# LPT3_5.net
KiCad netlist of a schematic drawn in EAGLE
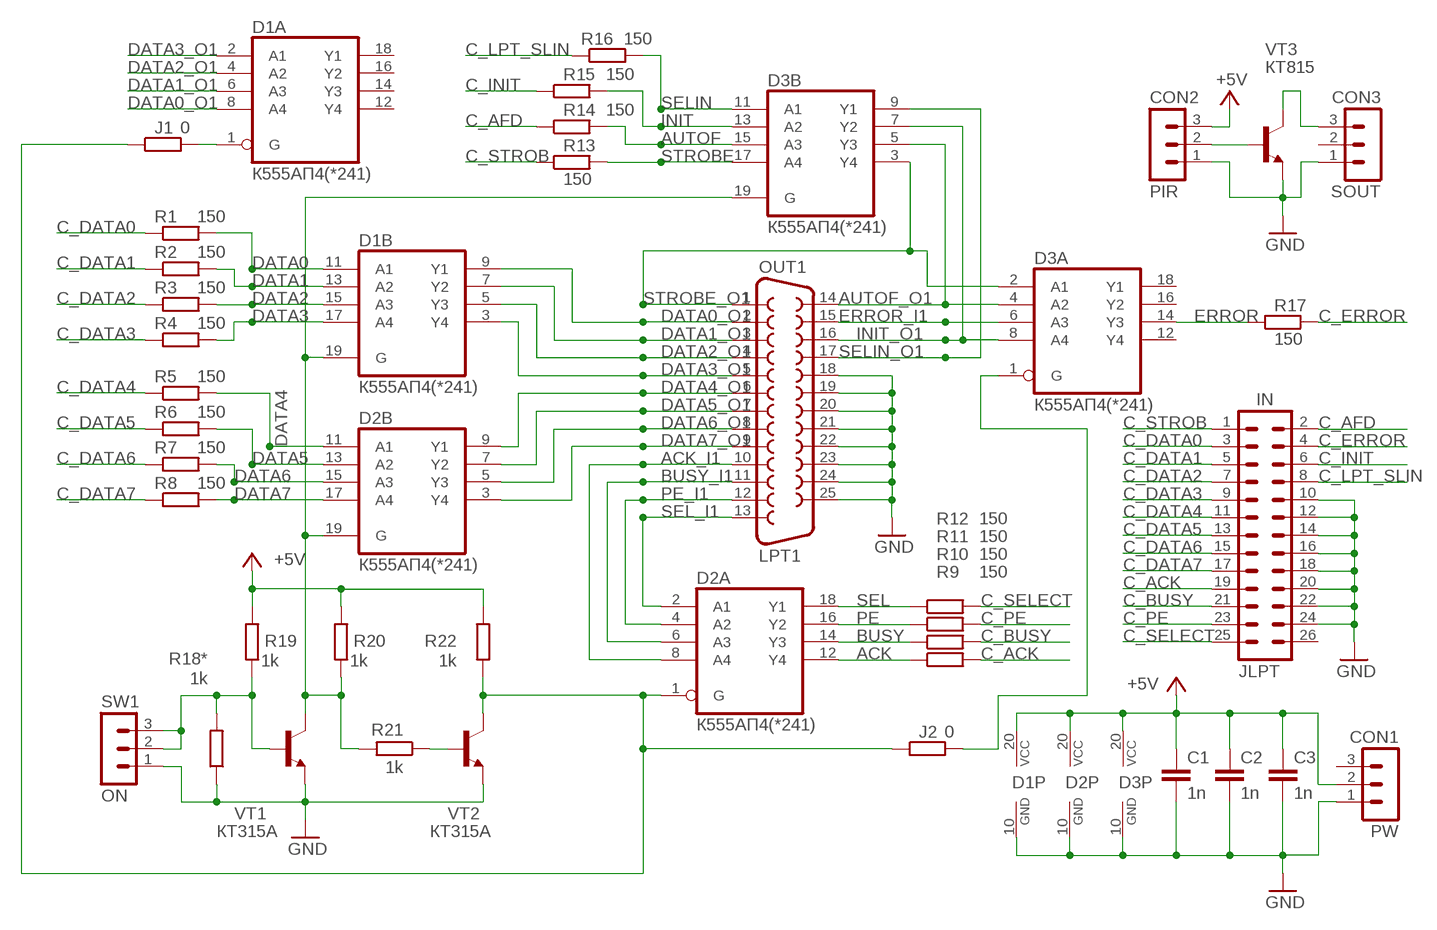
[diagram p0: schematic, sheet 1]

(export (version "E")
  (design (tool "Eeschema 10.0.6"))
  (components
    (comp (ref "C1")
      (value "1n")
      (footprint "eagle-import:C050-024X044")
      (libsource (lib "eagle-import") (part "C-EU050-024X044"))
    )
    (comp (ref "C2")
      (value "1n")
      (footprint "eagle-import:C075-032X103")
      (libsource (lib "eagle-import") (part "C-EU075-032X103"))
    )
    (comp (ref "C3")
      (value "1n")
      (footprint "eagle-import:C050-024X044")
      (libsource (lib "eagle-import") (part "C-EU050-024X044"))
    )
    (comp (ref "CON1")
      (value "PW")
      (footprint "eagle-import:MA03-1")
      (fields (field (name "OC_FARNELL") "unknown") (field (name "OC_NEWARK") "unknown"))
      (libsource (lib "eagle-import") (part "MA03-1"))
    )
    (comp (ref "CON2")
      (value "PIR")
      (footprint "eagle-import:MA03-1")
      (fields (field (name "OC_FARNELL") "unknown") (field (name "OC_NEWARK") "unknown"))
      (libsource (lib "eagle-import") (part "MA03-1"))
    )
    (comp (ref "CON3")
      (value "SOUT")
      (footprint "eagle-import:MA03-1")
      (fields (field (name "OC_FARNELL") "unknown") (field (name "OC_NEWARK") "unknown"))
      (libsource (lib "eagle-import") (part "MA03-1"))
    )
    (comp (ref "D1")
      (value "К555АП4(*241)")
      (footprint "eagle-import:DIL20")
      (libsource (lib "eagle-import") (part "74241NAC"))
    )
    (comp (ref "D2")
      (value "К555АП4(*241)")
      (footprint "eagle-import:DIL20")
      (libsource (lib "eagle-import") (part "74241NAC"))
    )
    (comp (ref "D3")
      (value "К555АП4(*241)")
      (footprint "eagle-import:DIL20")
      (libsource (lib "eagle-import") (part "74241NAC"))
    )
    (comp (ref "IN")
      (value "JLPT")
      (footprint "eagle-import:MA13-2")
      (libsource (lib "eagle-import") (part "MA13-2"))
    )
    (comp (ref "J1")
      (value "0")
      (footprint "eagle-import:R1206")
      (libsource (lib "eagle-import") (part "R-EU_R1206"))
    )
    (comp (ref "J2")
      (value "0")
      (footprint "eagle-import:R1206")
      (libsource (lib "eagle-import") (part "R-EU_R1206"))
    )
    (comp (ref "OUT1")
      (value "LPT1")
      (footprint "eagle-import:F25HP")
      (libsource (lib "eagle-import") (part "F25HP"))
    )
    (comp (ref "R1")
      (value "150")
      (footprint "eagle-import:0204_7")
      (libsource (lib "eagle-import") (part "R-EU_0204/7"))
    )
    (comp (ref "R2")
      (value "150")
      (footprint "eagle-import:0204_7")
      (libsource (lib "eagle-import") (part "R-EU_0204/7"))
    )
    (comp (ref "R3")
      (value "150")
      (footprint "eagle-import:0204_7")
      (libsource (lib "eagle-import") (part "R-EU_0204/7"))
    )
    (comp (ref "R4")
      (value "150")
      (footprint "eagle-import:0204_7")
      (libsource (lib "eagle-import") (part "R-EU_0204/7"))
    )
    (comp (ref "R5")
      (value "150")
      (footprint "eagle-import:0204_7")
      (libsource (lib "eagle-import") (part "R-EU_0204/7"))
    )
    (comp (ref "R6")
      (value "150")
      (footprint "eagle-import:0204_7")
      (libsource (lib "eagle-import") (part "R-EU_0204/7"))
    )
    (comp (ref "R7")
      (value "150")
      (footprint "eagle-import:0204_7")
      (libsource (lib "eagle-import") (part "R-EU_0204/7"))
    )
    (comp (ref "R8")
      (value "150")
      (footprint "eagle-import:0204_7")
      (libsource (lib "eagle-import") (part "R-EU_0204/7"))
    )
    (comp (ref "R9")
      (value "150")
      (footprint "eagle-import:0204_7")
      (libsource (lib "eagle-import") (part "R-EU_0204/7"))
    )
    (comp (ref "R10")
      (value "150")
      (footprint "eagle-import:0204_7")
      (libsource (lib "eagle-import") (part "R-EU_0204/7"))
    )
    (comp (ref "R11")
      (value "150")
      (footprint "eagle-import:0204_7")
      (libsource (lib "eagle-import") (part "R-EU_0204/7"))
    )
    (comp (ref "R12")
      (value "150")
      (footprint "eagle-import:0204_7")
      (libsource (lib "eagle-import") (part "R-EU_0204/7"))
    )
    (comp (ref "R13")
      (value "150")
      (footprint "eagle-import:M0805")
      (libsource (lib "eagle-import") (part "R-EU_M0805"))
    )
    (comp (ref "R14")
      (value "150")
      (footprint "eagle-import:M0805")
      (libsource (lib "eagle-import") (part "R-EU_M0805"))
    )
    (comp (ref "R15")
      (value "150")
      (footprint "eagle-import:M0805")
      (libsource (lib "eagle-import") (part "R-EU_M0805"))
    )
    (comp (ref "R16")
      (value "150")
      (footprint "eagle-import:M0805")
      (libsource (lib "eagle-import") (part "R-EU_M0805"))
    )
    (comp (ref "R17")
      (value "150")
      (footprint "eagle-import:M0805")
      (libsource (lib "eagle-import") (part "R-EU_M0805"))
    )
    (comp (ref "R18*")
      (value "1k")
      (footprint "eagle-import:M0805")
      (libsource (lib "eagle-import") (part "R-EU_M0805"))
    )
    (comp (ref "R19")
      (value "1k")
      (footprint "eagle-import:M1206")
      (libsource (lib "eagle-import") (part "R-EU_M1206"))
    )
    (comp (ref "R20")
      (value "1k")
      (footprint "eagle-import:M0805")
      (libsource (lib "eagle-import") (part "R-EU_M0805"))
    )
    (comp (ref "R21")
      (value "1k")
      (footprint "eagle-import:M0805")
      (libsource (lib "eagle-import") (part "R-EU_M0805"))
    )
    (comp (ref "R22")
      (value "1k")
      (footprint "eagle-import:M0805")
      (libsource (lib "eagle-import") (part "R-EU_M0805"))
    )
    (comp (ref "SW1")
      (value "ON")
      (footprint "eagle-import:MA03-1")
      (libsource (lib "eagle-import") (part "MA03-1"))
    )
    (comp (ref "VT1")
      (value "КТ315А")
      (footprint "eagle-import:TO92-ECB")
      (libsource (lib "eagle-import") (part "2SC1740"))
    )
    (comp (ref "VT2")
      (value "КТ315А")
      (footprint "eagle-import:TO92-ECB")
      (libsource (lib "eagle-import") (part "2SC1740"))
    )
    (comp (ref "VT3")
      (value "КТ815")
      (footprint "eagle-import:TO220BV")
      (libsource (lib "eagle-import") (part "2SC1306"))
    )
  )
  (nets
    (net (code "1") (name "+5V") (class "Default")
      (node (ref "C1") (pin "1") (pinfunction "1_1") (pintype "passive"))
      (node (ref "C2") (pin "1") (pinfunction "1_1") (pintype "passive"))
      (node (ref "C3") (pin "1") (pinfunction "1_1") (pintype "passive"))
      (node (ref "CON1") (pin "2") (pinfunction "2_2") (pintype "passive"))
      (node (ref "CON2") (pin "3") (pinfunction "3_3") (pintype "passive"))
      (node (ref "D1") (pin "20") (pinfunction "VCC_20") (pintype "power_in"))
      (node (ref "D2") (pin "20") (pinfunction "VCC_20") (pintype "power_in"))
      (node (ref "D3") (pin "20") (pinfunction "VCC_20") (pintype "power_in"))
      (node (ref "R19") (pin "2") (pinfunction "2_2") (pintype "passive"))
      (node (ref "R20") (pin "2") (pinfunction "2_2") (pintype "passive"))
      (node (ref "R22") (pin "2") (pinfunction "2_2") (pintype "passive"))
    )
    (net (code "2") (name "/ACK") (class "Default")
      (node (ref "D2") (pin "12") (pinfunction "Y4_12") (pintype "tri_state"))
      (node (ref "R9") (pin "1") (pinfunction "1_1") (pintype "passive"))
    )
    (net (code "3") (name "/ACK_I1") (class "Default")
      (node (ref "D2") (pin "8") (pinfunction "A4_8") (pintype "input"))
      (node (ref "OUT1") (pin "10") (pinfunction "10_10") (pintype "passive"))
    )
    (net (code "4") (name "/AUTOF") (class "Default")
      (node (ref "D3") (pin "15") (pinfunction "A3_15") (pintype "input"))
      (node (ref "R14") (pin "2") (pinfunction "2_2") (pintype "passive"))
    )
    (net (code "5") (name "/AUTOF_O1") (class "Default")
      (node (ref "D3") (pin "4") (pinfunction "A2_4") (pintype "input"))
      (node (ref "D3") (pin "5") (pinfunction "Y3_5") (pintype "tri_state"))
      (node (ref "OUT1") (pin "14") (pinfunction "14_14") (pintype "passive"))
    )
    (net (code "6") (name "/BUSY") (class "Default")
      (node (ref "D2") (pin "14") (pinfunction "Y3_14") (pintype "tri_state"))
      (node (ref "R10") (pin "1") (pinfunction "1_1") (pintype "passive"))
    )
    (net (code "7") (name "/BUSY_I1") (class "Default")
      (node (ref "D2") (pin "6") (pinfunction "A3_6") (pintype "input"))
      (node (ref "OUT1") (pin "11") (pinfunction "11_11") (pintype "passive"))
    )
    (net (code "8") (name "/C_ACK") (class "Default")
      (node (ref "IN") (pin "19") (pinfunction "19_19") (pintype "passive"))
      (node (ref "R9") (pin "2") (pinfunction "2_2") (pintype "passive"))
    )
    (net (code "9") (name "/C_AFD") (class "Default")
      (node (ref "IN") (pin "2") (pinfunction "2_2") (pintype "passive"))
      (node (ref "R14") (pin "1") (pinfunction "1_1") (pintype "passive"))
    )
    (net (code "10") (name "/C_BUSY") (class "Default")
      (node (ref "IN") (pin "21") (pinfunction "21_21") (pintype "passive"))
      (node (ref "R10") (pin "2") (pinfunction "2_2") (pintype "passive"))
    )
    (net (code "11") (name "/C_DATA0") (class "Default")
      (node (ref "IN") (pin "3") (pinfunction "3_3") (pintype "passive"))
      (node (ref "R1") (pin "1") (pinfunction "1_1") (pintype "passive"))
    )
    (net (code "12") (name "/C_DATA1") (class "Default")
      (node (ref "IN") (pin "5") (pinfunction "5_5") (pintype "passive"))
      (node (ref "R2") (pin "1") (pinfunction "1_1") (pintype "passive"))
    )
    (net (code "13") (name "/C_DATA2") (class "Default")
      (node (ref "IN") (pin "7") (pinfunction "7_7") (pintype "passive"))
      (node (ref "R3") (pin "1") (pinfunction "1_1") (pintype "passive"))
    )
    (net (code "14") (name "/C_DATA3") (class "Default")
      (node (ref "IN") (pin "9") (pinfunction "9_9") (pintype "passive"))
      (node (ref "R4") (pin "1") (pinfunction "1_1") (pintype "passive"))
    )
    (net (code "15") (name "/C_DATA4") (class "Default")
      (node (ref "IN") (pin "11") (pinfunction "11_11") (pintype "passive"))
      (node (ref "R5") (pin "1") (pinfunction "1_1") (pintype "passive"))
    )
    (net (code "16") (name "/C_DATA5") (class "Default")
      (node (ref "IN") (pin "13") (pinfunction "13_13") (pintype "passive"))
      (node (ref "R6") (pin "1") (pinfunction "1_1") (pintype "passive"))
    )
    (net (code "17") (name "/C_DATA6") (class "Default")
      (node (ref "IN") (pin "15") (pinfunction "15_15") (pintype "passive"))
      (node (ref "R7") (pin "1") (pinfunction "1_1") (pintype "passive"))
    )
    (net (code "18") (name "/C_DATA7") (class "Default")
      (node (ref "IN") (pin "17") (pinfunction "17_17") (pintype "passive"))
      (node (ref "R8") (pin "1") (pinfunction "1_1") (pintype "passive"))
    )
    (net (code "19") (name "/C_ERROR") (class "Default")
      (node (ref "IN") (pin "4") (pinfunction "4_4") (pintype "passive"))
      (node (ref "R17") (pin "2") (pinfunction "2_2") (pintype "passive"))
    )
    (net (code "20") (name "/C_INIT") (class "Default")
      (node (ref "IN") (pin "6") (pinfunction "6_6") (pintype "passive"))
      (node (ref "R15") (pin "1") (pinfunction "1_1") (pintype "passive"))
    )
    (net (code "21") (name "/C_LPT_SLIN") (class "Default")
      (node (ref "IN") (pin "8") (pinfunction "8_8") (pintype "passive"))
      (node (ref "R16") (pin "1") (pinfunction "1_1") (pintype "passive"))
    )
    (net (code "22") (name "/C_PE") (class "Default")
      (node (ref "IN") (pin "23") (pinfunction "23_23") (pintype "passive"))
      (node (ref "R11") (pin "2") (pinfunction "2_2") (pintype "passive"))
    )
    (net (code "23") (name "/C_SELECT") (class "Default")
      (node (ref "IN") (pin "25") (pinfunction "25_25") (pintype "passive"))
      (node (ref "R12") (pin "2") (pinfunction "2_2") (pintype "passive"))
    )
    (net (code "24") (name "/C_STROB") (class "Default")
      (node (ref "IN") (pin "1") (pinfunction "1_1") (pintype "passive"))
      (node (ref "R13") (pin "1") (pinfunction "1_1") (pintype "passive"))
    )
    (net (code "25") (name "/DATA0") (class "Default")
      (node (ref "D1") (pin "11") (pinfunction "A1_11") (pintype "input"))
      (node (ref "R1") (pin "2") (pinfunction "2_2") (pintype "passive"))
    )
    (net (code "26") (name "/DATA0_O1") (class "Default")
      (node (ref "D1") (pin "8") (pinfunction "A4_8") (pintype "input"))
      (node (ref "D1") (pin "9") (pinfunction "Y1_9") (pintype "tri_state"))
      (node (ref "OUT1") (pin "2") (pinfunction "2_2") (pintype "passive"))
    )
    (net (code "27") (name "/DATA1") (class "Default")
      (node (ref "D1") (pin "13") (pinfunction "A2_13") (pintype "input"))
      (node (ref "R2") (pin "2") (pinfunction "2_2") (pintype "passive"))
    )
    (net (code "28") (name "/DATA1_O1") (class "Default")
      (node (ref "D1") (pin "6") (pinfunction "A3_6") (pintype "input"))
      (node (ref "D1") (pin "7") (pinfunction "Y2_7") (pintype "tri_state"))
      (node (ref "OUT1") (pin "3") (pinfunction "3_3") (pintype "passive"))
    )
    (net (code "29") (name "/DATA2") (class "Default")
      (node (ref "D1") (pin "15") (pinfunction "A3_15") (pintype "input"))
      (node (ref "R3") (pin "2") (pinfunction "2_2") (pintype "passive"))
    )
    (net (code "30") (name "/DATA2_O1") (class "Default")
      (node (ref "D1") (pin "4") (pinfunction "A2_4") (pintype "input"))
      (node (ref "D1") (pin "5") (pinfunction "Y3_5") (pintype "tri_state"))
      (node (ref "OUT1") (pin "4") (pinfunction "4_4") (pintype "passive"))
    )
    (net (code "31") (name "/DATA3") (class "Default")
      (node (ref "D1") (pin "17") (pinfunction "A4_17") (pintype "input"))
      (node (ref "R4") (pin "2") (pinfunction "2_2") (pintype "passive"))
    )
    (net (code "32") (name "/DATA3_O1") (class "Default")
      (node (ref "D1") (pin "2") (pinfunction "A1_2") (pintype "input"))
      (node (ref "D1") (pin "3") (pinfunction "Y4_3") (pintype "tri_state"))
      (node (ref "OUT1") (pin "5") (pinfunction "5_5") (pintype "passive"))
    )
    (net (code "33") (name "/DATA4") (class "Default")
      (node (ref "D2") (pin "11") (pinfunction "A1_11") (pintype "input"))
      (node (ref "R5") (pin "2") (pinfunction "2_2") (pintype "passive"))
    )
    (net (code "34") (name "/DATA4_O1") (class "Default")
      (node (ref "D2") (pin "9") (pinfunction "Y1_9") (pintype "tri_state"))
      (node (ref "OUT1") (pin "6") (pinfunction "6_6") (pintype "passive"))
    )
    (net (code "35") (name "/DATA5") (class "Default")
      (node (ref "D2") (pin "13") (pinfunction "A2_13") (pintype "input"))
      (node (ref "R6") (pin "2") (pinfunction "2_2") (pintype "passive"))
    )
    (net (code "36") (name "/DATA5_O1") (class "Default")
      (node (ref "D2") (pin "7") (pinfunction "Y2_7") (pintype "tri_state"))
      (node (ref "OUT1") (pin "7") (pinfunction "7_7") (pintype "passive"))
    )
    (net (code "37") (name "/DATA6") (class "Default")
      (node (ref "D2") (pin "15") (pinfunction "A3_15") (pintype "input"))
      (node (ref "R7") (pin "2") (pinfunction "2_2") (pintype "passive"))
    )
    (net (code "38") (name "/DATA6_O1") (class "Default")
      (node (ref "D2") (pin "5") (pinfunction "Y3_5") (pintype "tri_state"))
      (node (ref "OUT1") (pin "8") (pinfunction "8_8") (pintype "passive"))
    )
    (net (code "39") (name "/DATA7") (class "Default")
      (node (ref "D2") (pin "17") (pinfunction "A4_17") (pintype "input"))
      (node (ref "R8") (pin "2") (pinfunction "2_2") (pintype "passive"))
    )
    (net (code "40") (name "/DATA7_O1") (class "Default")
      (node (ref "D2") (pin "3") (pinfunction "Y4_3") (pintype "tri_state"))
      (node (ref "OUT1") (pin "9") (pinfunction "9_9") (pintype "passive"))
    )
    (net (code "41") (name "/ERROR") (class "Default")
      (node (ref "D3") (pin "14") (pinfunction "Y3_14") (pintype "tri_state"))
      (node (ref "R17") (pin "1") (pinfunction "1_1") (pintype "passive"))
    )
    (net (code "42") (name "/ERROR_I1") (class "Default")
      (node (ref "D3") (pin "6") (pinfunction "A3_6") (pintype "input"))
      (node (ref "OUT1") (pin "15") (pinfunction "15_15") (pintype "passive"))
    )
    (net (code "43") (name "/INIT") (class "Default")
      (node (ref "D3") (pin "13") (pinfunction "A2_13") (pintype "input"))
      (node (ref "R15") (pin "2") (pinfunction "2_2") (pintype "passive"))
    )
    (net (code "44") (name "/INIT_O1") (class "Default")
      (node (ref "D3") (pin "7") (pinfunction "Y2_7") (pintype "tri_state"))
      (node (ref "D3") (pin "8") (pinfunction "A4_8") (pintype "input"))
      (node (ref "OUT1") (pin "16") (pinfunction "16_16") (pintype "passive"))
    )
    (net (code "45") (name "/PE") (class "Default")
      (node (ref "D2") (pin "16") (pinfunction "Y2_16") (pintype "tri_state"))
      (node (ref "R11") (pin "1") (pinfunction "1_1") (pintype "passive"))
    )
    (net (code "46") (name "/PE_I1") (class "Default")
      (node (ref "D2") (pin "4") (pinfunction "A2_4") (pintype "input"))
      (node (ref "OUT1") (pin "12") (pinfunction "12_12") (pintype "passive"))
    )
    (net (code "47") (name "/SEL") (class "Default")
      (node (ref "D2") (pin "18") (pinfunction "Y1_18") (pintype "tri_state"))
      (node (ref "R12") (pin "1") (pinfunction "1_1") (pintype "passive"))
    )
    (net (code "48") (name "/SELIN") (class "Default")
      (node (ref "D3") (pin "11") (pinfunction "A1_11") (pintype "input"))
      (node (ref "R16") (pin "2") (pinfunction "2_2") (pintype "passive"))
    )
    (net (code "49") (name "/SELIN_O1") (class "Default")
      (node (ref "D3") (pin "9") (pinfunction "Y1_9") (pintype "tri_state"))
      (node (ref "OUT1") (pin "17") (pinfunction "17_17") (pintype "passive"))
    )
    (net (code "50") (name "/SEL_I1") (class "Default")
      (node (ref "D2") (pin "2") (pinfunction "A1_2") (pintype "input"))
      (node (ref "OUT1") (pin "13") (pinfunction "13_13") (pintype "passive"))
    )
    (net (code "51") (name "/STROBE") (class "Default")
      (node (ref "D3") (pin "17") (pinfunction "A4_17") (pintype "input"))
      (node (ref "R13") (pin "2") (pinfunction "2_2") (pintype "passive"))
    )
    (net (code "52") (name "/STROBE_O1") (class "Default")
      (node (ref "D3") (pin "2") (pinfunction "A1_2") (pintype "input"))
      (node (ref "D3") (pin "3") (pinfunction "Y4_3") (pintype "tri_state"))
      (node (ref "OUT1") (pin "1") (pinfunction "1_1") (pintype "passive"))
    )
    (net (code "53") (name "GND") (class "Default")
      (node (ref "C1") (pin "2") (pinfunction "2_2") (pintype "passive"))
      (node (ref "C2") (pin "2") (pinfunction "2_2") (pintype "passive"))
      (node (ref "C3") (pin "2") (pinfunction "2_2") (pintype "passive"))
      (node (ref "CON1") (pin "1") (pinfunction "1_1") (pintype "passive"))
      (node (ref "CON2") (pin "1") (pinfunction "1_1") (pintype "passive"))
      (node (ref "CON3") (pin "1") (pinfunction "1_1") (pintype "passive"))
      (node (ref "D1") (pin "10") (pinfunction "GND_10") (pintype "power_in"))
      (node (ref "D2") (pin "10") (pinfunction "GND_10") (pintype "power_in"))
      (node (ref "D3") (pin "10") (pinfunction "GND_10") (pintype "power_in"))
      (node (ref "IN") (pin "10") (pinfunction "10_10") (pintype "passive"))
      (node (ref "IN") (pin "12") (pinfunction "12_12") (pintype "passive"))
      (node (ref "IN") (pin "14") (pinfunction "14_14") (pintype "passive"))
      (node (ref "IN") (pin "16") (pinfunction "16_16") (pintype "passive"))
      (node (ref "IN") (pin "18") (pinfunction "18_18") (pintype "passive"))
      (node (ref "IN") (pin "20") (pinfunction "20_20") (pintype "passive"))
      (node (ref "IN") (pin "22") (pinfunction "22_22") (pintype "passive"))
      (node (ref "IN") (pin "24") (pinfunction "24_24") (pintype "passive"))
      (node (ref "OUT1") (pin "18") (pinfunction "18_18") (pintype "passive"))
      (node (ref "OUT1") (pin "19") (pinfunction "19_19") (pintype "passive"))
      (node (ref "OUT1") (pin "20") (pinfunction "20_20") (pintype "passive"))
      (node (ref "OUT1") (pin "21") (pinfunction "21_21") (pintype "passive"))
      (node (ref "OUT1") (pin "22") (pinfunction "22_22") (pintype "passive"))
      (node (ref "OUT1") (pin "23") (pinfunction "23_23") (pintype "passive"))
      (node (ref "OUT1") (pin "24") (pinfunction "24_24") (pintype "passive"))
      (node (ref "OUT1") (pin "25") (pinfunction "25_25") (pintype "passive"))
      (node (ref "R18*") (pin "1") (pinfunction "1_1") (pintype "passive"))
      (node (ref "SW1") (pin "1") (pinfunction "1_1") (pintype "passive"))
      (node (ref "VT1") (pin "E") (pinfunction "E_E") (pintype "passive"))
      (node (ref "VT2") (pin "E") (pinfunction "E_E") (pintype "passive"))
      (node (ref "VT3") (pin "3") (pinfunction "E_3") (pintype "passive"))
    )
    (net (code "54") (name "Net-(D1A-G)") (class "Default")
      (node (ref "D1") (pin "1") (pinfunction "G_1") (pintype "input"))
      (node (ref "J1") (pin "2") (pinfunction "2_2") (pintype "passive"))
    )
    (net (code "55") (name "Net-(D1B-G)") (class "Default")
      (node (ref "D1") (pin "19") (pinfunction "G_19") (pintype "input"))
      (node (ref "D2") (pin "19") (pinfunction "G_19") (pintype "input"))
      (node (ref "D3") (pin "19") (pinfunction "G_19") (pintype "input"))
      (node (ref "R20") (pin "1") (pinfunction "1_1") (pintype "passive"))
      (node (ref "R21") (pin "2") (pinfunction "2_2") (pintype "passive"))
      (node (ref "VT1") (pin "C") (pinfunction "C_C") (pintype "passive"))
    )
    (net (code "56") (name "Net-(D2A-G)") (class "Default")
      (node (ref "D2") (pin "1") (pinfunction "G_1") (pintype "input"))
      (node (ref "J1") (pin "1") (pinfunction "1_1") (pintype "passive"))
      (node (ref "J2") (pin "1") (pinfunction "1_1") (pintype "passive"))
      (node (ref "R22") (pin "1") (pinfunction "1_1") (pintype "passive"))
      (node (ref "VT2") (pin "C") (pinfunction "C_C") (pintype "passive"))
    )
    (net (code "57") (name "Net-(D3A-G)") (class "Default")
      (node (ref "D3") (pin "1") (pinfunction "G_1") (pintype "input"))
      (node (ref "J2") (pin "2") (pinfunction "2_2") (pintype "passive"))
    )
    (net (code "58") (name "Net-(R18*-Pad2)") (class "Default")
      (node (ref "R18*") (pin "2") (pinfunction "2_2") (pintype "passive"))
      (node (ref "R19") (pin "1") (pinfunction "1_1") (pintype "passive"))
      (node (ref "SW1") (pin "2") (pinfunction "2_2") (pintype "passive"))
      (node (ref "SW1") (pin "3") (pinfunction "3_3") (pintype "passive"))
      (node (ref "VT1") (pin "B") (pinfunction "B_B") (pintype "passive"))
    )
    (net (code "59") (name "Net-(R21-Pad1)") (class "Default")
      (node (ref "R21") (pin "1") (pinfunction "1_1") (pintype "passive"))
      (node (ref "VT2") (pin "B") (pinfunction "B_B") (pintype "passive"))
    )
    (net (code "60") (name "Net-(VT3-B)") (class "Default")
      (node (ref "CON2") (pin "2") (pinfunction "2_2") (pintype "passive"))
      (node (ref "VT3") (pin "1") (pinfunction "B_1") (pintype "passive"))
    )
    (net (code "61") (name "Net-(VT3-C)") (class "Default")
      (node (ref "CON3") (pin "3") (pinfunction "3_3") (pintype "passive"))
      (node (ref "VT3") (pin "2") (pinfunction "C_2") (pintype "passive"))
    )
    (net (code "62") (name "unconnected-(CON1-Pad3)") (class "Default")
      (node (ref "CON1") (pin "3") (pinfunction "3_3") (pintype "passive"))
    )
    (net (code "63") (name "unconnected-(CON3-Pad2)") (class "Default")
      (node (ref "CON3") (pin "2") (pinfunction "2_2") (pintype "passive"))
    )
    (net (code "64") (name "unconnected-(D1A-Y1-Pad18)") (class "Default")
      (node (ref "D1") (pin "18") (pinfunction "Y1_18") (pintype "tri_state"))
    )
    (net (code "65") (name "unconnected-(D1A-Y2-Pad16)") (class "Default")
      (node (ref "D1") (pin "16") (pinfunction "Y2_16") (pintype "tri_state"))
    )
    (net (code "66") (name "unconnected-(D1A-Y3-Pad14)") (class "Default")
      (node (ref "D1") (pin "14") (pinfunction "Y3_14") (pintype "tri_state"))
    )
    (net (code "67") (name "unconnected-(D1A-Y4-Pad12)") (class "Default")
      (node (ref "D1") (pin "12") (pinfunction "Y4_12") (pintype "tri_state"))
    )
    (net (code "68") (name "unconnected-(D3A-Y1-Pad18)") (class "Default")
      (node (ref "D3") (pin "18") (pinfunction "Y1_18") (pintype "tri_state"))
    )
    (net (code "69") (name "unconnected-(D3A-Y2-Pad16)") (class "Default")
      (node (ref "D3") (pin "16") (pinfunction "Y2_16") (pintype "tri_state"))
    )
    (net (code "70") (name "unconnected-(D3A-Y4-Pad12)") (class "Default")
      (node (ref "D3") (pin "12") (pinfunction "Y4_12") (pintype "tri_state"))
    )
    (net (code "71") (name "unconnected-(IN-Pad26)") (class "Default")
      (node (ref "IN") (pin "26") (pinfunction "26_26") (pintype "passive"))
    )
  )
)
